# Gloves_PCB.net
KiCad netlist of a schematic drawn in EAGLE
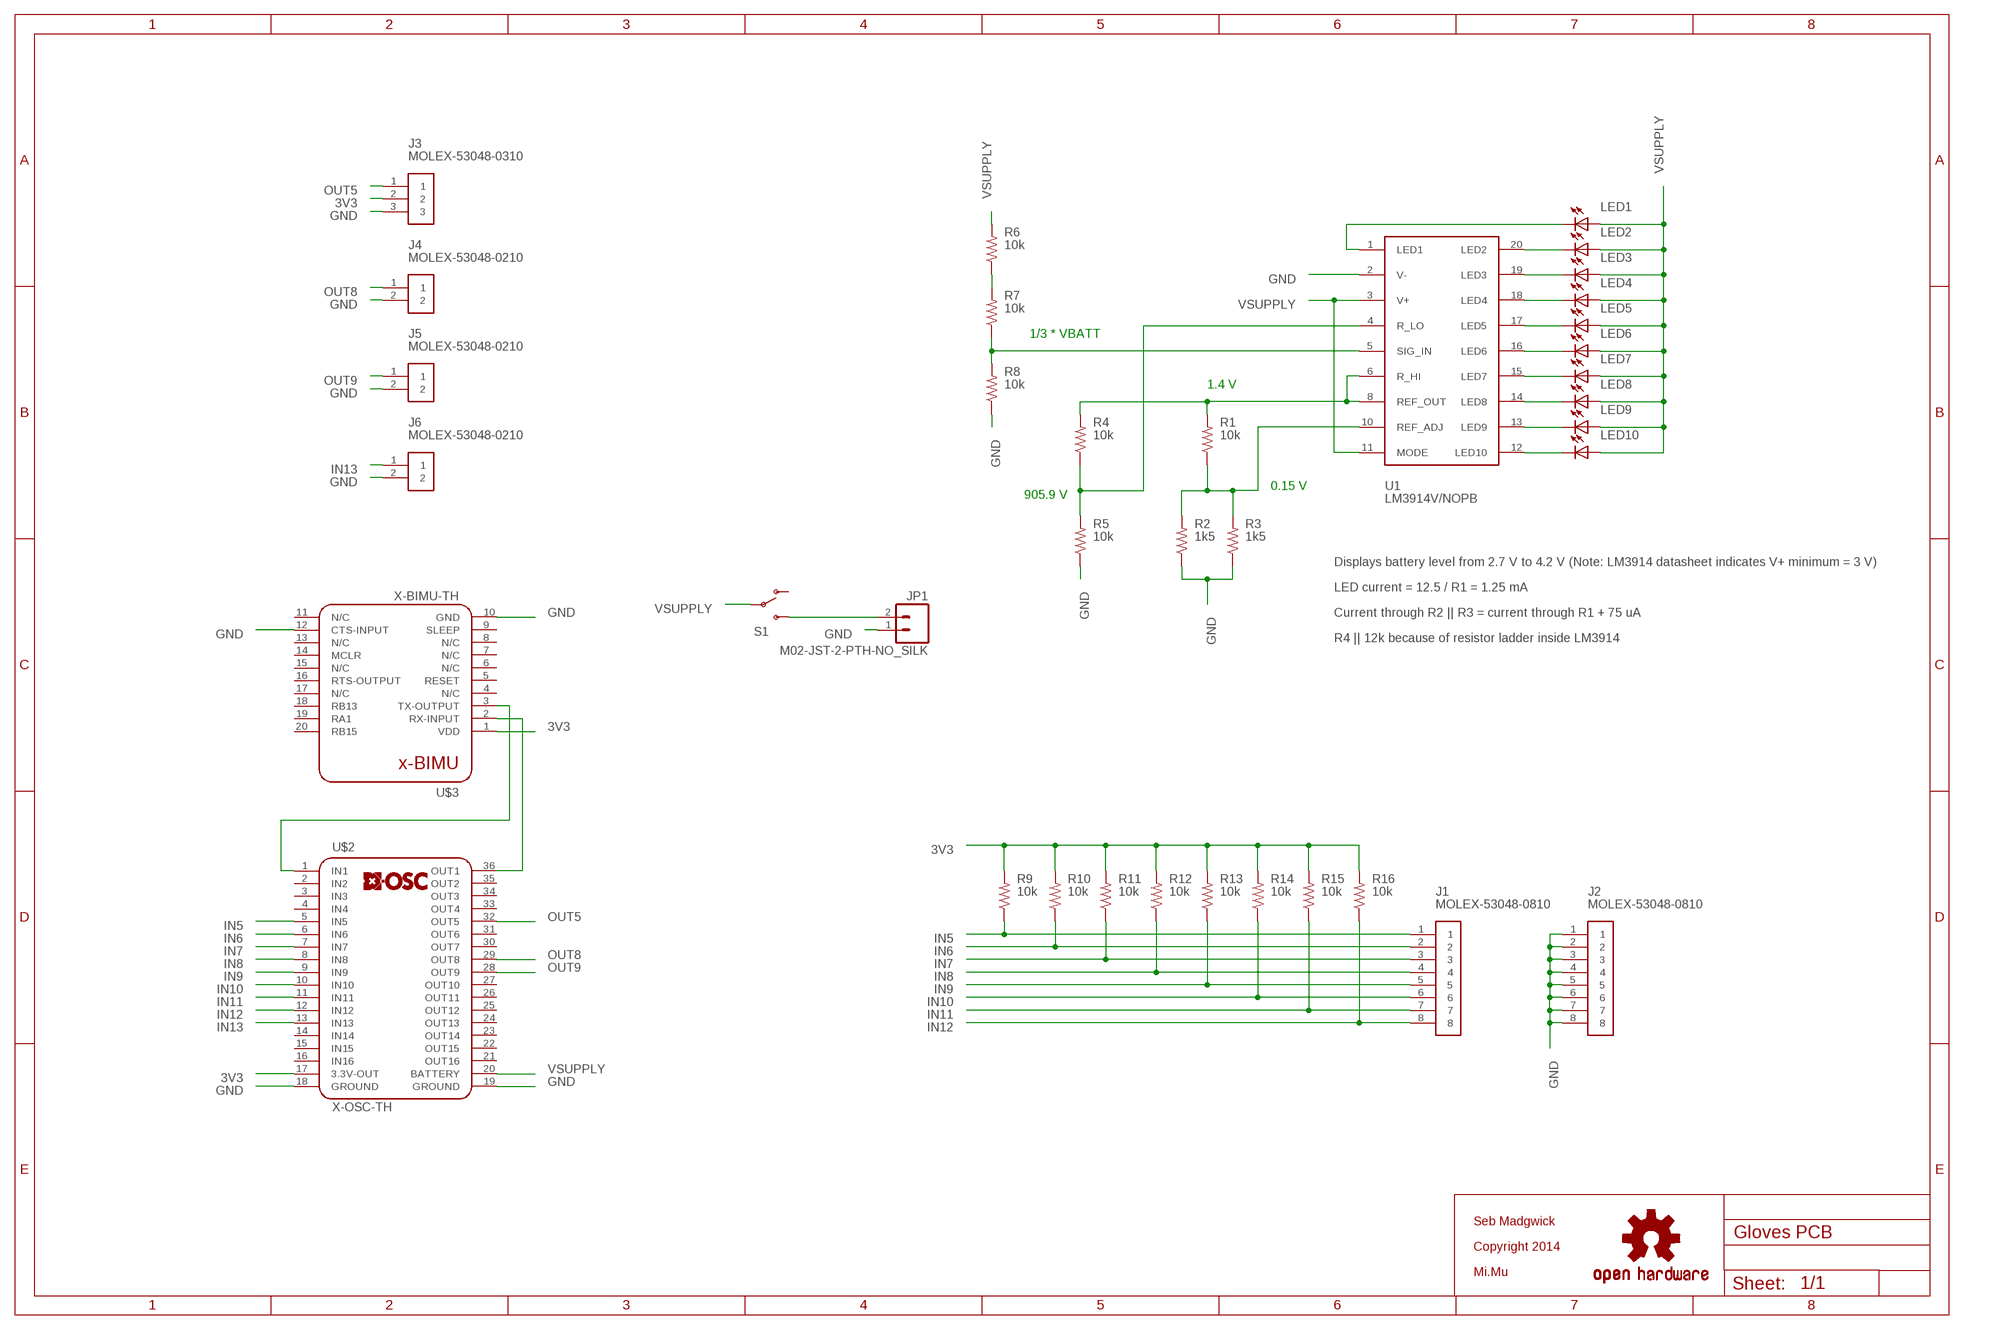
[diagram p0: schematic, sheet 1]

(export (version "E")
  (design (tool "Eeschema 10.0.6"))
  (components
    (comp (ref "J1")
      (value "MOLEX-53048-0810")
      (footprint "eagle-import:MOLEX-53048-0810")
      (libsource (lib "eagle-import") (part "MOLEX-53048-0810"))
    )
    (comp (ref "J2")
      (value "MOLEX-53048-0810")
      (footprint "eagle-import:MOLEX-53048-0810")
      (libsource (lib "eagle-import") (part "MOLEX-53048-0810"))
    )
    (comp (ref "J3")
      (value "MOLEX-53048-0310")
      (footprint "eagle-import:MOLEX-53048-0310")
      (libsource (lib "eagle-import") (part "MOLEX-53048-0310"))
    )
    (comp (ref "J4")
      (value "MOLEX-53048-0210")
      (footprint "eagle-import:MOLEX-53048-0210")
      (libsource (lib "eagle-import") (part "MOLEX-53048-0210"))
    )
    (comp (ref "J5")
      (value "MOLEX-53048-0210")
      (footprint "eagle-import:MOLEX-53048-0210")
      (libsource (lib "eagle-import") (part "MOLEX-53048-0210"))
    )
    (comp (ref "J6")
      (value "MOLEX-53048-0210")
      (footprint "eagle-import:MOLEX-53048-0210")
      (libsource (lib "eagle-import") (part "MOLEX-53048-0210"))
    )
    (comp (ref "JP1")
      (value "M02-JST-2-PTH-NO_SILK")
      (footprint "eagle-import:JST-2-PTH-NS")
      (libsource (lib "eagle-import") (part "M02-JST-2-PTH-NO_SILK"))
    )
    (comp (ref "LED1")
      (value "LEDCHIPLED_1206")
      (footprint "eagle-import:CHIPLED_1206")
      (libsource (lib "eagle-import") (part "LEDCHIPLED_1206"))
    )
    (comp (ref "LED2")
      (value "LEDCHIPLED_1206")
      (footprint "eagle-import:CHIPLED_1206")
      (libsource (lib "eagle-import") (part "LEDCHIPLED_1206"))
    )
    (comp (ref "LED3")
      (value "LEDCHIPLED_1206")
      (footprint "eagle-import:CHIPLED_1206")
      (libsource (lib "eagle-import") (part "LEDCHIPLED_1206"))
    )
    (comp (ref "LED4")
      (value "LEDCHIPLED_1206")
      (footprint "eagle-import:CHIPLED_1206")
      (libsource (lib "eagle-import") (part "LEDCHIPLED_1206"))
    )
    (comp (ref "LED5")
      (value "LEDCHIPLED_1206")
      (footprint "eagle-import:CHIPLED_1206")
      (libsource (lib "eagle-import") (part "LEDCHIPLED_1206"))
    )
    (comp (ref "LED6")
      (value "LEDCHIPLED_1206")
      (footprint "eagle-import:CHIPLED_1206")
      (libsource (lib "eagle-import") (part "LEDCHIPLED_1206"))
    )
    (comp (ref "LED7")
      (value "LEDCHIPLED_1206")
      (footprint "eagle-import:CHIPLED_1206")
      (libsource (lib "eagle-import") (part "LEDCHIPLED_1206"))
    )
    (comp (ref "LED8")
      (value "LEDCHIPLED_1206")
      (footprint "eagle-import:CHIPLED_1206")
      (libsource (lib "eagle-import") (part "LEDCHIPLED_1206"))
    )
    (comp (ref "LED9")
      (value "LEDCHIPLED_1206")
      (footprint "eagle-import:CHIPLED_1206")
      (libsource (lib "eagle-import") (part "LEDCHIPLED_1206"))
    )
    (comp (ref "LED10")
      (value "LEDCHIPLED_1206")
      (footprint "eagle-import:CHIPLED_1206")
      (libsource (lib "eagle-import") (part "LEDCHIPLED_1206"))
    )
    (comp (ref "R1")
      (value "10k")
      (footprint "eagle-import:0805")
      (libsource (lib "eagle-import") (part "RESISTOR0805-RES"))
    )
    (comp (ref "R2")
      (value "1k5")
      (footprint "eagle-import:0805")
      (libsource (lib "eagle-import") (part "RESISTOR0805-RES"))
    )
    (comp (ref "R3")
      (value "1k5")
      (footprint "eagle-import:0805")
      (libsource (lib "eagle-import") (part "RESISTOR0805-RES"))
    )
    (comp (ref "R4")
      (value "10k")
      (footprint "eagle-import:0805")
      (libsource (lib "eagle-import") (part "RESISTOR0805-RES"))
    )
    (comp (ref "R5")
      (value "10k")
      (footprint "eagle-import:0805")
      (libsource (lib "eagle-import") (part "RESISTOR0805-RES"))
    )
    (comp (ref "R6")
      (value "10k")
      (footprint "eagle-import:0805")
      (libsource (lib "eagle-import") (part "RESISTOR0805-RES"))
    )
    (comp (ref "R7")
      (value "10k")
      (footprint "eagle-import:0805")
      (libsource (lib "eagle-import") (part "RESISTOR0805-RES"))
    )
    (comp (ref "R8")
      (value "10k")
      (footprint "eagle-import:0805")
      (libsource (lib "eagle-import") (part "RESISTOR0805-RES"))
    )
    (comp (ref "R9")
      (value "10k")
      (footprint "eagle-import:0805")
      (libsource (lib "eagle-import") (part "RESISTOR0805-RES"))
    )
    (comp (ref "R10")
      (value "10k")
      (footprint "eagle-import:0805")
      (libsource (lib "eagle-import") (part "RESISTOR0805-RES"))
    )
    (comp (ref "R11")
      (value "10k")
      (footprint "eagle-import:0805")
      (libsource (lib "eagle-import") (part "RESISTOR0805-RES"))
    )
    (comp (ref "R12")
      (value "10k")
      (footprint "eagle-import:0805")
      (libsource (lib "eagle-import") (part "RESISTOR0805-RES"))
    )
    (comp (ref "R13")
      (value "10k")
      (footprint "eagle-import:0805")
      (libsource (lib "eagle-import") (part "RESISTOR0805-RES"))
    )
    (comp (ref "R14")
      (value "10k")
      (footprint "eagle-import:0805")
      (libsource (lib "eagle-import") (part "RESISTOR0805-RES"))
    )
    (comp (ref "R15")
      (value "10k")
      (footprint "eagle-import:0805")
      (libsource (lib "eagle-import") (part "RESISTOR0805-RES"))
    )
    (comp (ref "R16")
      (value "10k")
      (footprint "eagle-import:0805")
      (libsource (lib "eagle-import") (part "RESISTOR0805-RES"))
    )
    (comp (ref "S1")
      (value "SWITCH-DPST")
      (footprint "eagle-import:WURTH-ELEKTRONIK-450301014042")
      (libsource (lib "eagle-import") (part "SWITCH-DPST"))
    )
    (comp (ref "U$1")
      (value "OSHW-LOGOS")
      (footprint "eagle-import:OSHW-LOGO-S")
      (libsource (lib "eagle-import") (part "OSHW-LOGOS"))
    )
    (comp (ref "U$2")
      (value "X-OSC-TH")
      (footprint "eagle-import:X-OSC_TH")
      (libsource (lib "eagle-import") (part "X-OSC-TH"))
    )
    (comp (ref "U$3")
      (value "X-BIMU-TH")
      (footprint "eagle-import:X-BIMU_TH")
      (libsource (lib "eagle-import") (part "X-BIMU-TH"))
    )
    (comp (ref "U1")
      (value "LM3914V/NOPB")
      (footprint "eagle-import:PLCC-20")
      (libsource (lib "eagle-import") (part "LM3914PLCC"))
    )
  )
  (nets
    (net (code "1") (name "/3V3") (class "Default")
      (node (ref "J3") (pin "2") (pinfunction "2_2") (pintype "bidirectional"))
      (node (ref "R10") (pin "2") (pinfunction "2_2") (pintype "passive"))
      (node (ref "R11") (pin "2") (pinfunction "2_2") (pintype "passive"))
      (node (ref "R12") (pin "2") (pinfunction "2_2") (pintype "passive"))
      (node (ref "R13") (pin "2") (pinfunction "2_2") (pintype "passive"))
      (node (ref "R14") (pin "2") (pinfunction "2_2") (pintype "passive"))
      (node (ref "R15") (pin "2") (pinfunction "2_2") (pintype "passive"))
      (node (ref "R16") (pin "2") (pinfunction "2_2") (pintype "passive"))
      (node (ref "R9") (pin "2") (pinfunction "2_2") (pintype "passive"))
      (node (ref "U$2") (pin "17") (pinfunction "3.3V-OUT_17") (pintype "bidirectional"))
      (node (ref "U$3") (pin "1") (pinfunction "VDD_1") (pintype "bidirectional"))
    )
    (net (code "2") (name "/GND") (class "Default")
      (node (ref "J2") (pin "1") (pinfunction "1_1") (pintype "bidirectional"))
      (node (ref "J2") (pin "2") (pinfunction "2_2") (pintype "bidirectional"))
      (node (ref "J2") (pin "3") (pinfunction "3_3") (pintype "bidirectional"))
      (node (ref "J2") (pin "4") (pinfunction "4_4") (pintype "bidirectional"))
      (node (ref "J2") (pin "5") (pinfunction "5_5") (pintype "bidirectional"))
      (node (ref "J2") (pin "6") (pinfunction "6_6") (pintype "bidirectional"))
      (node (ref "J2") (pin "7") (pinfunction "7_7") (pintype "bidirectional"))
      (node (ref "J2") (pin "8") (pinfunction "8_8") (pintype "bidirectional"))
      (node (ref "J3") (pin "3") (pinfunction "3_3") (pintype "bidirectional"))
      (node (ref "J4") (pin "2") (pinfunction "2_2") (pintype "bidirectional"))
      (node (ref "J5") (pin "2") (pinfunction "2_2") (pintype "bidirectional"))
      (node (ref "J6") (pin "2") (pinfunction "2_2") (pintype "bidirectional"))
      (node (ref "JP1") (pin "1") (pinfunction "1_1") (pintype "passive"))
      (node (ref "R2") (pin "1") (pinfunction "1_1") (pintype "passive"))
      (node (ref "R3") (pin "1") (pinfunction "1_1") (pintype "passive"))
      (node (ref "R5") (pin "1") (pinfunction "1_1") (pintype "passive"))
      (node (ref "R8") (pin "1") (pinfunction "1_1") (pintype "passive"))
      (node (ref "U$2") (pin "18") (pinfunction "GROUND_18") (pintype "bidirectional"))
      (node (ref "U$2") (pin "19") (pinfunction "GROUND_19") (pintype "bidirectional"))
      (node (ref "U$3") (pin "10") (pinfunction "GND_10") (pintype "bidirectional"))
      (node (ref "U$3") (pin "12") (pinfunction "CTS-INPUT_12") (pintype "bidirectional"))
      (node (ref "U1") (pin "2") (pinfunction "V-_2") (pintype "bidirectional"))
    )
    (net (code "3") (name "/IN5") (class "Default")
      (node (ref "J1") (pin "1") (pinfunction "1_1") (pintype "bidirectional"))
      (node (ref "R9") (pin "1") (pinfunction "1_1") (pintype "passive"))
      (node (ref "U$2") (pin "5") (pinfunction "IN5_5") (pintype "bidirectional"))
    )
    (net (code "4") (name "/IN6") (class "Default")
      (node (ref "J1") (pin "2") (pinfunction "2_2") (pintype "bidirectional"))
      (node (ref "R10") (pin "1") (pinfunction "1_1") (pintype "passive"))
      (node (ref "U$2") (pin "6") (pinfunction "IN6_6") (pintype "bidirectional"))
    )
    (net (code "5") (name "/IN7") (class "Default")
      (node (ref "J1") (pin "3") (pinfunction "3_3") (pintype "bidirectional"))
      (node (ref "R11") (pin "1") (pinfunction "1_1") (pintype "passive"))
      (node (ref "U$2") (pin "7") (pinfunction "IN7_7") (pintype "bidirectional"))
    )
    (net (code "6") (name "/IN8") (class "Default")
      (node (ref "J1") (pin "4") (pinfunction "4_4") (pintype "bidirectional"))
      (node (ref "R12") (pin "1") (pinfunction "1_1") (pintype "passive"))
      (node (ref "U$2") (pin "8") (pinfunction "IN8_8") (pintype "bidirectional"))
    )
    (net (code "7") (name "/IN9") (class "Default")
      (node (ref "J1") (pin "5") (pinfunction "5_5") (pintype "bidirectional"))
      (node (ref "R13") (pin "1") (pinfunction "1_1") (pintype "passive"))
      (node (ref "U$2") (pin "9") (pinfunction "IN9_9") (pintype "bidirectional"))
    )
    (net (code "8") (name "/IN10") (class "Default")
      (node (ref "J1") (pin "6") (pinfunction "6_6") (pintype "bidirectional"))
      (node (ref "R14") (pin "1") (pinfunction "1_1") (pintype "passive"))
      (node (ref "U$2") (pin "10") (pinfunction "IN10_10") (pintype "bidirectional"))
    )
    (net (code "9") (name "/IN11") (class "Default")
      (node (ref "J1") (pin "7") (pinfunction "7_7") (pintype "bidirectional"))
      (node (ref "R15") (pin "1") (pinfunction "1_1") (pintype "passive"))
      (node (ref "U$2") (pin "11") (pinfunction "IN11_11") (pintype "bidirectional"))
    )
    (net (code "10") (name "/IN12") (class "Default")
      (node (ref "J1") (pin "8") (pinfunction "8_8") (pintype "bidirectional"))
      (node (ref "R16") (pin "1") (pinfunction "1_1") (pintype "passive"))
      (node (ref "U$2") (pin "12") (pinfunction "IN12_12") (pintype "bidirectional"))
    )
    (net (code "11") (name "/IN13") (class "Default")
      (node (ref "J6") (pin "1") (pinfunction "1_1") (pintype "bidirectional"))
      (node (ref "U$2") (pin "13") (pinfunction "IN13_13") (pintype "bidirectional"))
    )
    (net (code "12") (name "/OUT5") (class "Default")
      (node (ref "J3") (pin "1") (pinfunction "1_1") (pintype "bidirectional"))
      (node (ref "U$2") (pin "32") (pinfunction "OUT5_32") (pintype "bidirectional"))
    )
    (net (code "13") (name "/OUT8") (class "Default")
      (node (ref "J4") (pin "1") (pinfunction "1_1") (pintype "bidirectional"))
      (node (ref "U$2") (pin "29") (pinfunction "OUT8_29") (pintype "bidirectional"))
    )
    (net (code "14") (name "/OUT9") (class "Default")
      (node (ref "J5") (pin "1") (pinfunction "1_1") (pintype "bidirectional"))
      (node (ref "U$2") (pin "28") (pinfunction "OUT9_28") (pintype "bidirectional"))
    )
    (net (code "15") (name "/VSUPPLY") (class "Default")
      (node (ref "LED1") (pin "A") (pinfunction "A_A") (pintype "passive"))
      (node (ref "LED10") (pin "A") (pinfunction "A_A") (pintype "passive"))
      (node (ref "LED2") (pin "A") (pinfunction "A_A") (pintype "passive"))
      (node (ref "LED3") (pin "A") (pinfunction "A_A") (pintype "passive"))
      (node (ref "LED4") (pin "A") (pinfunction "A_A") (pintype "passive"))
      (node (ref "LED5") (pin "A") (pinfunction "A_A") (pintype "passive"))
      (node (ref "LED6") (pin "A") (pinfunction "A_A") (pintype "passive"))
      (node (ref "LED7") (pin "A") (pinfunction "A_A") (pintype "passive"))
      (node (ref "LED8") (pin "A") (pinfunction "A_A") (pintype "passive"))
      (node (ref "LED9") (pin "A") (pinfunction "A_A") (pintype "passive"))
      (node (ref "R6") (pin "2") (pinfunction "2_2") (pintype "passive"))
      (node (ref "S1") (pin "2") (pinfunction "2_2") (pintype "passive"))
      (node (ref "U$2") (pin "20") (pinfunction "BATTERY_20") (pintype "bidirectional"))
      (node (ref "U1") (pin "11") (pinfunction "MODE_11") (pintype "bidirectional"))
      (node (ref "U1") (pin "3") (pinfunction "V+_3") (pintype "bidirectional"))
    )
    (net (code "16") (name "Net-(JP1-Pad2)") (class "Default")
      (node (ref "JP1") (pin "2") (pinfunction "2_2") (pintype "passive"))
      (node (ref "S1") (pin "3") (pinfunction "3_3") (pintype "passive"))
    )
    (net (code "17") (name "Net-(R6-Pad1)") (class "Default")
      (node (ref "R6") (pin "1") (pinfunction "1_1") (pintype "passive"))
      (node (ref "R7") (pin "2") (pinfunction "2_2") (pintype "passive"))
    )
    (net (code "18") (name "Net-(U$2-IN1)") (class "Default")
      (node (ref "U$2") (pin "1") (pinfunction "IN1_1") (pintype "bidirectional"))
      (node (ref "U$3") (pin "3") (pinfunction "TX-OUTPUT_3") (pintype "bidirectional"))
    )
    (net (code "19") (name "Net-(U$2-OUT1)") (class "Default")
      (node (ref "U$2") (pin "36") (pinfunction "OUT1_36") (pintype "bidirectional"))
      (node (ref "U$3") (pin "2") (pinfunction "RX-INPUT_2") (pintype "bidirectional"))
    )
    (net (code "20") (name "Net-(U1-LED1)") (class "Default")
      (node (ref "LED1") (pin "C") (pinfunction "C_C") (pintype "passive"))
      (node (ref "U1") (pin "1") (pinfunction "LED1_1") (pintype "bidirectional"))
    )
    (net (code "21") (name "Net-(U1-LED2)") (class "Default")
      (node (ref "LED2") (pin "C") (pinfunction "C_C") (pintype "passive"))
      (node (ref "U1") (pin "20") (pinfunction "LED2_20") (pintype "bidirectional"))
    )
    (net (code "22") (name "Net-(U1-LED3)") (class "Default")
      (node (ref "LED3") (pin "C") (pinfunction "C_C") (pintype "passive"))
      (node (ref "U1") (pin "19") (pinfunction "LED3_19") (pintype "bidirectional"))
    )
    (net (code "23") (name "Net-(U1-LED4)") (class "Default")
      (node (ref "LED4") (pin "C") (pinfunction "C_C") (pintype "passive"))
      (node (ref "U1") (pin "18") (pinfunction "LED4_18") (pintype "bidirectional"))
    )
    (net (code "24") (name "Net-(U1-LED5)") (class "Default")
      (node (ref "LED5") (pin "C") (pinfunction "C_C") (pintype "passive"))
      (node (ref "U1") (pin "17") (pinfunction "LED5_17") (pintype "bidirectional"))
    )
    (net (code "25") (name "Net-(U1-LED6)") (class "Default")
      (node (ref "LED6") (pin "C") (pinfunction "C_C") (pintype "passive"))
      (node (ref "U1") (pin "16") (pinfunction "LED6_16") (pintype "bidirectional"))
    )
    (net (code "26") (name "Net-(U1-LED7)") (class "Default")
      (node (ref "LED7") (pin "C") (pinfunction "C_C") (pintype "passive"))
      (node (ref "U1") (pin "15") (pinfunction "LED7_15") (pintype "bidirectional"))
    )
    (net (code "27") (name "Net-(U1-LED8)") (class "Default")
      (node (ref "LED8") (pin "C") (pinfunction "C_C") (pintype "passive"))
      (node (ref "U1") (pin "14") (pinfunction "LED8_14") (pintype "bidirectional"))
    )
    (net (code "28") (name "Net-(U1-LED9)") (class "Default")
      (node (ref "LED9") (pin "C") (pinfunction "C_C") (pintype "passive"))
      (node (ref "U1") (pin "13") (pinfunction "LED9_13") (pintype "bidirectional"))
    )
    (net (code "29") (name "Net-(U1-LED10)") (class "Default")
      (node (ref "LED10") (pin "C") (pinfunction "C_C") (pintype "passive"))
      (node (ref "U1") (pin "12") (pinfunction "LED10_12") (pintype "bidirectional"))
    )
    (net (code "30") (name "Net-(U1-REF_ADJ)") (class "Default")
      (node (ref "R1") (pin "1") (pinfunction "1_1") (pintype "passive"))
      (node (ref "R2") (pin "2") (pinfunction "2_2") (pintype "passive"))
      (node (ref "R3") (pin "2") (pinfunction "2_2") (pintype "passive"))
      (node (ref "U1") (pin "10") (pinfunction "REF_ADJ_10") (pintype "bidirectional"))
    )
    (net (code "31") (name "Net-(U1-REF_OUT)") (class "Default")
      (node (ref "R1") (pin "2") (pinfunction "2_2") (pintype "passive"))
      (node (ref "R4") (pin "2") (pinfunction "2_2") (pintype "passive"))
      (node (ref "U1") (pin "6") (pinfunction "R_HI_6") (pintype "bidirectional"))
      (node (ref "U1") (pin "8") (pinfunction "REF_OUT_8") (pintype "bidirectional"))
    )
    (net (code "32") (name "Net-(U1-R_LO)") (class "Default")
      (node (ref "R4") (pin "1") (pinfunction "1_1") (pintype "passive"))
      (node (ref "R5") (pin "2") (pinfunction "2_2") (pintype "passive"))
      (node (ref "U1") (pin "4") (pinfunction "R_LO_4") (pintype "bidirectional"))
    )
    (net (code "33") (name "Net-(U1-SIG_IN)") (class "Default")
      (node (ref "R7") (pin "1") (pinfunction "1_1") (pintype "passive"))
      (node (ref "R8") (pin "2") (pinfunction "2_2") (pintype "passive"))
      (node (ref "U1") (pin "5") (pinfunction "SIG_IN_5") (pintype "bidirectional"))
    )
    (net (code "34") (name "unconnected-(S1-Pad1)") (class "Default")
      (node (ref "S1") (pin "1") (pinfunction "1_1") (pintype "passive"))
    )
    (net (code "35") (name "unconnected-(U$2-IN2-Pad2)") (class "Default")
      (node (ref "U$2") (pin "2") (pinfunction "IN2_2") (pintype "bidirectional"))
    )
    (net (code "36") (name "unconnected-(U$2-IN3-Pad3)") (class "Default")
      (node (ref "U$2") (pin "3") (pinfunction "IN3_3") (pintype "bidirectional"))
    )
    (net (code "37") (name "unconnected-(U$2-IN4-Pad4)") (class "Default")
      (node (ref "U$2") (pin "4") (pinfunction "IN4_4") (pintype "bidirectional"))
    )
    (net (code "38") (name "unconnected-(U$2-IN14-Pad14)") (class "Default")
      (node (ref "U$2") (pin "14") (pinfunction "IN14_14") (pintype "bidirectional"))
    )
    (net (code "39") (name "unconnected-(U$2-IN15-Pad15)") (class "Default")
      (node (ref "U$2") (pin "15") (pinfunction "IN15_15") (pintype "bidirectional"))
    )
    (net (code "40") (name "unconnected-(U$2-IN16-Pad16)") (class "Default")
      (node (ref "U$2") (pin "16") (pinfunction "IN16_16") (pintype "bidirectional"))
    )
    (net (code "41") (name "unconnected-(U$2-OUT2-Pad35)") (class "Default")
      (node (ref "U$2") (pin "35") (pinfunction "OUT2_35") (pintype "bidirectional"))
    )
    (net (code "42") (name "unconnected-(U$2-OUT3-Pad34)") (class "Default")
      (node (ref "U$2") (pin "34") (pinfunction "OUT3_34") (pintype "bidirectional"))
    )
    (net (code "43") (name "unconnected-(U$2-OUT4-Pad33)") (class "Default")
      (node (ref "U$2") (pin "33") (pinfunction "OUT4_33") (pintype "bidirectional"))
    )
    (net (code "44") (name "unconnected-(U$2-OUT6-Pad31)") (class "Default")
      (node (ref "U$2") (pin "31") (pinfunction "OUT6_31") (pintype "bidirectional"))
    )
    (net (code "45") (name "unconnected-(U$2-OUT7-Pad30)") (class "Default")
      (node (ref "U$2") (pin "30") (pinfunction "OUT7_30") (pintype "bidirectional"))
    )
    (net (code "46") (name "unconnected-(U$2-OUT10-Pad27)") (class "Default")
      (node (ref "U$2") (pin "27") (pinfunction "OUT10_27") (pintype "bidirectional"))
    )
    (net (code "47") (name "unconnected-(U$2-OUT11-Pad26)") (class "Default")
      (node (ref "U$2") (pin "26") (pinfunction "OUT11_26") (pintype "bidirectional"))
    )
    (net (code "48") (name "unconnected-(U$2-OUT12-Pad25)") (class "Default")
      (node (ref "U$2") (pin "25") (pinfunction "OUT12_25") (pintype "bidirectional"))
    )
    (net (code "49") (name "unconnected-(U$2-OUT13-Pad24)") (class "Default")
      (node (ref "U$2") (pin "24") (pinfunction "OUT13_24") (pintype "bidirectional"))
    )
    (net (code "50") (name "unconnected-(U$2-OUT14-Pad23)") (class "Default")
      (node (ref "U$2") (pin "23") (pinfunction "OUT14_23") (pintype "bidirectional"))
    )
    (net (code "51") (name "unconnected-(U$2-OUT15-Pad22)") (class "Default")
      (node (ref "U$2") (pin "22") (pinfunction "OUT15_22") (pintype "bidirectional"))
    )
    (net (code "52") (name "unconnected-(U$2-OUT16-Pad21)") (class "Default")
      (node (ref "U$2") (pin "21") (pinfunction "OUT16_21") (pintype "bidirectional"))
    )
    (net (code "53") (name "unconnected-(U$3-MCLR-Pad14)") (class "Default")
      (node (ref "U$3") (pin "14") (pinfunction "MCLR_14") (pintype "bidirectional"))
    )
    (net (code "54") (name "unconnected-(U$3-N{slash}C-Pad4)") (class "Default")
      (node (ref "U$3") (pin "4") (pinfunction "N/C_4") (pintype "bidirectional"))
    )
    (net (code "55") (name "unconnected-(U$3-N{slash}C-Pad6)") (class "Default")
      (node (ref "U$3") (pin "6") (pinfunction "N/C_6") (pintype "bidirectional"))
    )
    (net (code "56") (name "unconnected-(U$3-N{slash}C-Pad7)") (class "Default")
      (node (ref "U$3") (pin "7") (pinfunction "N/C_7") (pintype "bidirectional"))
    )
    (net (code "57") (name "unconnected-(U$3-N{slash}C-Pad8)") (class "Default")
      (node (ref "U$3") (pin "8") (pinfunction "N/C_8") (pintype "bidirectional"))
    )
    (net (code "58") (name "unconnected-(U$3-N{slash}C-Pad11)") (class "Default")
      (node (ref "U$3") (pin "11") (pinfunction "N/C_11") (pintype "bidirectional"))
    )
    (net (code "59") (name "unconnected-(U$3-N{slash}C-Pad13)") (class "Default")
      (node (ref "U$3") (pin "13") (pinfunction "N/C_13") (pintype "bidirectional"))
    )
    (net (code "60") (name "unconnected-(U$3-N{slash}C-Pad15)") (class "Default")
      (node (ref "U$3") (pin "15") (pinfunction "N/C_15") (pintype "bidirectional"))
    )
    (net (code "61") (name "unconnected-(U$3-N{slash}C-Pad17)") (class "Default")
      (node (ref "U$3") (pin "17") (pinfunction "N/C_17") (pintype "bidirectional"))
    )
    (net (code "62") (name "unconnected-(U$3-RA1-Pad19)") (class "Default")
      (node (ref "U$3") (pin "19") (pinfunction "RA1_19") (pintype "bidirectional"))
    )
    (net (code "63") (name "unconnected-(U$3-RB13-Pad18)") (class "Default")
      (node (ref "U$3") (pin "18") (pinfunction "RB13_18") (pintype "bidirectional"))
    )
    (net (code "64") (name "unconnected-(U$3-RB15-Pad20)") (class "Default")
      (node (ref "U$3") (pin "20") (pinfunction "RB15_20") (pintype "bidirectional"))
    )
    (net (code "65") (name "unconnected-(U$3-RESET-Pad5)") (class "Default")
      (node (ref "U$3") (pin "5") (pinfunction "RESET_5") (pintype "bidirectional"))
    )
    (net (code "66") (name "unconnected-(U$3-RTS-OUTPUT-Pad16)") (class "Default")
      (node (ref "U$3") (pin "16") (pinfunction "RTS-OUTPUT_16") (pintype "bidirectional"))
    )
    (net (code "67") (name "unconnected-(U$3-SLEEP-Pad9)") (class "Default")
      (node (ref "U$3") (pin "9") (pinfunction "SLEEP_9") (pintype "bidirectional"))
    )
  )
)
